# BATT_BUTTONS.net
KiCad netlist of a schematic drawn in EAGLE
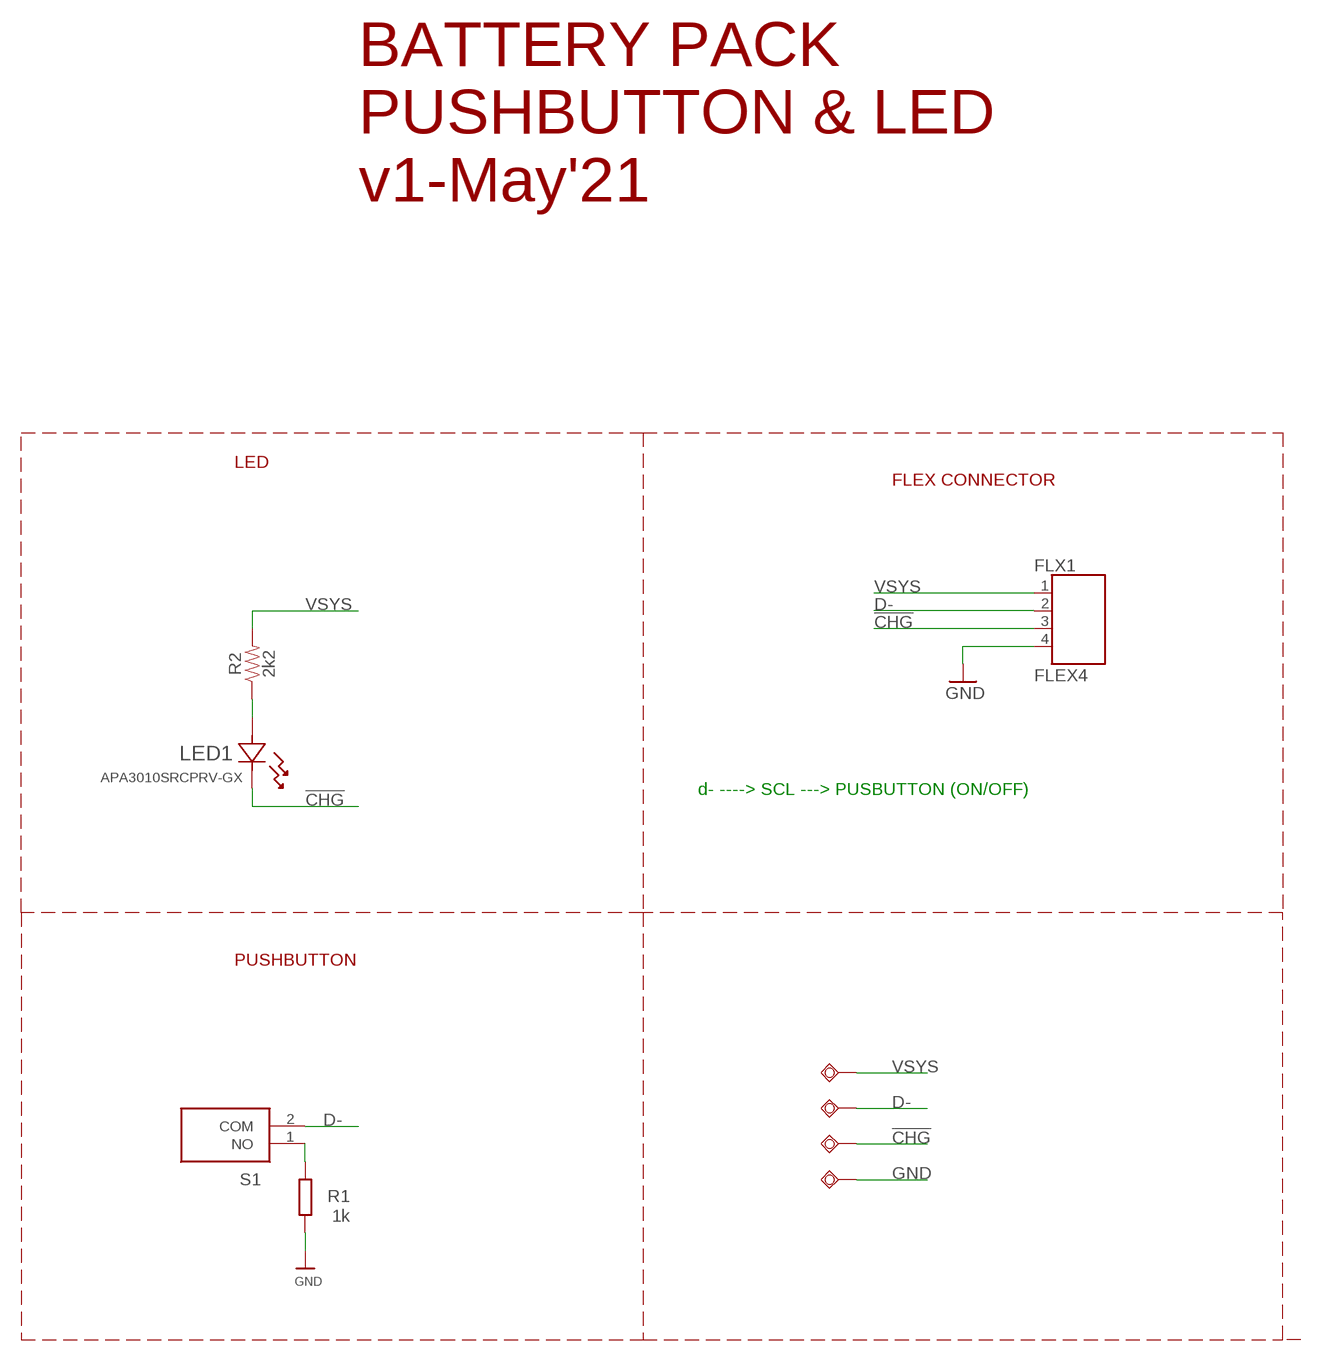
[diagram p0: schematic, sheet 1]

(export (version "E")
  (design (tool "Eeschema 10.0.6"))
  (components
    (comp (ref "!CHG")
      (value "TESTPAD_TPSQB1,27")
      (footprint "eagle-import:TESTPAD_B1,27")
      (libsource (lib "eagle-import") (part "TESTPAD_TPSQB1,27"))
    )
    (comp (ref "D-")
      (value "TESTPAD_TPSQB1,27")
      (footprint "eagle-import:TESTPAD_B1,27")
      (libsource (lib "eagle-import") (part "TESTPAD_TPSQB1,27"))
    )
    (comp (ref "FLX1")
      (value "FLEX4")
      (footprint "eagle-import:FLEX4")
      (libsource (lib "eagle-import") (part "FLEX4"))
    )
    (comp (ref "GND")
      (value "TESTPAD_TPSQB1,27")
      (footprint "eagle-import:TESTPAD_B1,27")
      (libsource (lib "eagle-import") (part "TESTPAD_TPSQB1,27"))
    )
    (comp (ref "LED1")
      (value "APA3010SRCPRV-GX")
      (footprint "eagle-import:LED_APA3010SRCPRV-GX_KNB")
      (fields (field (name "COPYRIGHT") "Copyright (C) 2018 Accelerated Designs. All rights reserved"))
      (libsource (lib "eagle-import") (part "APA3010SRCPRV-GX"))
    )
    (comp (ref "R1")
      (value "1k")
      (footprint "eagle-import:R0603")
      (libsource (lib "eagle-import") (part "R-EU_R0603"))
    )
    (comp (ref "R2")
      (value "2k2")
      (footprint "eagle-import:0402")
      (libsource (lib "eagle-import") (part "RESISTOR0402"))
    )
    (comp (ref "S1")
      (value "KXT311LHS")
      (footprint "eagle-import:KXT311LHS")
      (fields (field (name "MOUSER_PART_NUMBER") "611-KXT311LHS"))
      (libsource (lib "eagle-import") (part "KXT311LHS"))
    )
    (comp (ref "VSYS")
      (value "TESTPAD_TPSQB1,27")
      (footprint "eagle-import:TESTPAD_B1,27")
      (libsource (lib "eagle-import") (part "TESTPAD_TPSQB1,27"))
    )
  )
  (nets
    (net (code "1") (name "/D-") (class "Default")
      (node (ref "D-") (pin "TP") (pinfunction "TP_TP") (pintype "input"))
      (node (ref "FLX1") (pin "2") (pinfunction "2_2") (pintype "passive"))
      (node (ref "S1") (pin "2") (pinfunction "COM_2") (pintype "bidirectional"))
    )
    (net (code "2") (name "/VSYS") (class "Default")
      (node (ref "FLX1") (pin "1") (pinfunction "1_1") (pintype "passive"))
      (node (ref "R2") (pin "2") (pinfunction "2_2") (pintype "passive"))
      (node (ref "VSYS") (pin "TP") (pinfunction "TP_TP") (pintype "input"))
    )
    (net (code "3") (name "/~{CHG}") (class "Default")
      (node (ref "!CHG") (pin "TP") (pinfunction "TP_TP") (pintype "input"))
      (node (ref "FLX1") (pin "3") (pinfunction "3_3") (pintype "passive"))
      (node (ref "LED1") (pin "1") (pinfunction "1_1") (pintype "passive"))
    )
    (net (code "4") (name "GND") (class "Default")
      (node (ref "FLX1") (pin "4") (pinfunction "4_4") (pintype "passive"))
      (node (ref "GND") (pin "TP") (pinfunction "TP_TP") (pintype "input"))
      (node (ref "R1") (pin "1") (pinfunction "1_1") (pintype "passive"))
    )
    (net (code "5") (name "Net-(LED1-Pad2)") (class "Default")
      (node (ref "LED1") (pin "2") (pinfunction "2_2") (pintype "passive"))
      (node (ref "R2") (pin "1") (pinfunction "1_1") (pintype "passive"))
    )
    (net (code "6") (name "Net-(S1-NO)") (class "Default")
      (node (ref "R1") (pin "2") (pinfunction "2_2") (pintype "passive"))
      (node (ref "S1") (pin "1") (pinfunction "NO_1") (pintype "bidirectional"))
    )
  )
)
